# mag_pos_con_FX-30.net
KiCad netlist of a schematic drawn in Altium Designer
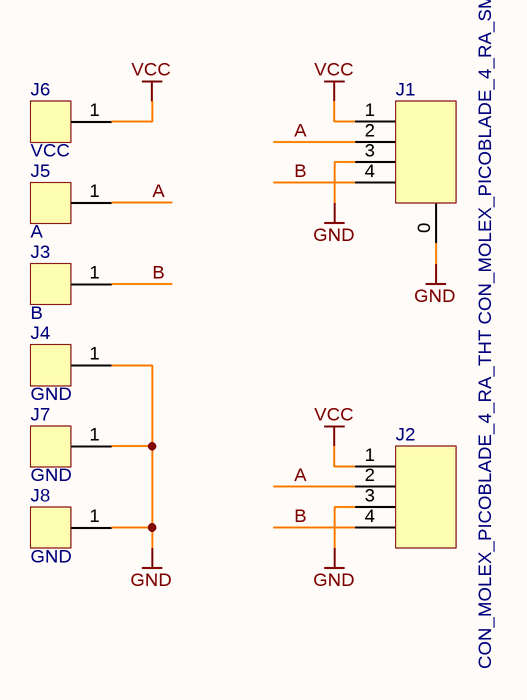
[diagram p0: mag_pos_con_FX-30.SchDoc]

(export (version "E")
  (design (tool "Eeschema 10.0.6"))
  (components
    (comp (ref "J1")
      (value "CON_MOLEX_PICOBLADE_4_RA_SMT")
      (footprint "mag_pos:CON_MOLEX_PICOBLADE_4_RA_SMT")
      (description "Molex Picoblade, 4 pins, Right Angle, SMT, 532617004")
      (libsource (lib "mag_pos") (part "CON_MOLEX_PICOBLADE_4_RA_SMT"))
    )
    (comp (ref "J2")
      (value "CON_MOLEX_PICOBLADE_4_RA_THT")
      (footprint "mag_pos:CON_MOLEX_PICOBLADE_4_RA_THT")
      (description "Molex Picoblade, 4 pins, Right Angle, THT, 532617004")
      (libsource (lib "mag_pos") (part "CON_MOLEX_PICOBLADE_4_RA_THT"))
    )
    (comp (ref "J3")
      (value "B")
      (footprint "mag_pos:CON_1X1_WIRE_0.034MM2_RELIEF")
      (description "0.034mm^2 wire with strain relief")
      (libsource (lib "") (part "Wire_0.034MM2_RELIEF_1"))
    )
    (comp (ref "J4")
      (value "GND")
      (footprint "mag_pos:CON_1X1_WIRE_0.034MM2_RELIEF")
      (description "0.034mm^2 wire with strain relief")
      (libsource (lib "mag_pos") (part "Wire_0.034MM2_RELIEF"))
    )
    (comp (ref "J5")
      (value "A")
      (footprint "mag_pos:CON_1X1_WIRE_0.034MM2_RELIEF")
      (description "0.034mm^2 wire with strain relief")
      (libsource (lib "") (part "Wire_0.034MM2_RELIEF_1"))
    )
    (comp (ref "J6")
      (value "VCC")
      (footprint "mag_pos:CON_1X1_WIRE_0.034MM2_RELIEF")
      (description "0.034mm^2 wire with strain relief")
      (libsource (lib "mag_pos") (part "Wire_0.034MM2_RELIEF"))
    )
    (comp (ref "J7")
      (value "GND")
      (footprint "mag_pos:CON_1X1_WIRE_0.5MM2_RELIEF")
      (description "0.5mm^2 wire with strain relief")
      (libsource (lib "mag_pos") (part "Wire_0.5MM2_RELIEF"))
    )
    (comp (ref "J8")
      (value "GND")
      (footprint "mag_pos:CON_1X1_WIRE_0.5MM2_RELIEF")
      (description "0.5mm^2 wire with strain relief")
      (libsource (lib "mag_pos") (part "Wire_0.5MM2_RELIEF"))
    )
  )
  (nets
    (net (code "1") (name "/A") (class "Default")
      (node (ref "J1") (pin "2") (pinfunction "2_2") (pintype "passive"))
      (node (ref "J2") (pin "2") (pinfunction "2_2") (pintype "passive"))
      (node (ref "J5") (pin "1") (pinfunction "1_1") (pintype "passive"))
    )
    (net (code "2") (name "/B") (class "Default")
      (node (ref "J1") (pin "4") (pinfunction "4_4") (pintype "passive"))
      (node (ref "J2") (pin "4") (pinfunction "4_4") (pintype "passive"))
      (node (ref "J3") (pin "1") (pinfunction "1_1") (pintype "passive"))
    )
    (net (code "3") (name "GND") (class "Default")
      (node (ref "J1") (pin "0") (pinfunction "0_0") (pintype "passive"))
      (node (ref "J1") (pin "3") (pinfunction "3_3") (pintype "passive"))
      (node (ref "J2") (pin "3") (pinfunction "3_3") (pintype "passive"))
      (node (ref "J4") (pin "1") (pinfunction "1_1") (pintype "passive"))
      (node (ref "J7") (pin "1") (pinfunction "1_1") (pintype "passive"))
      (node (ref "J8") (pin "1") (pinfunction "1_1") (pintype "passive"))
    )
    (net (code "4") (name "VCC") (class "Default")
      (node (ref "J1") (pin "1") (pinfunction "1_1") (pintype "passive"))
      (node (ref "J2") (pin "1") (pinfunction "1_1") (pintype "passive"))
      (node (ref "J6") (pin "1") (pinfunction "1_1") (pintype "passive"))
    )
  )
)
